# Controller_-_ESP32_Wroom_-_Rev_0_9.net
KiCad netlist of a schematic drawn in EAGLE
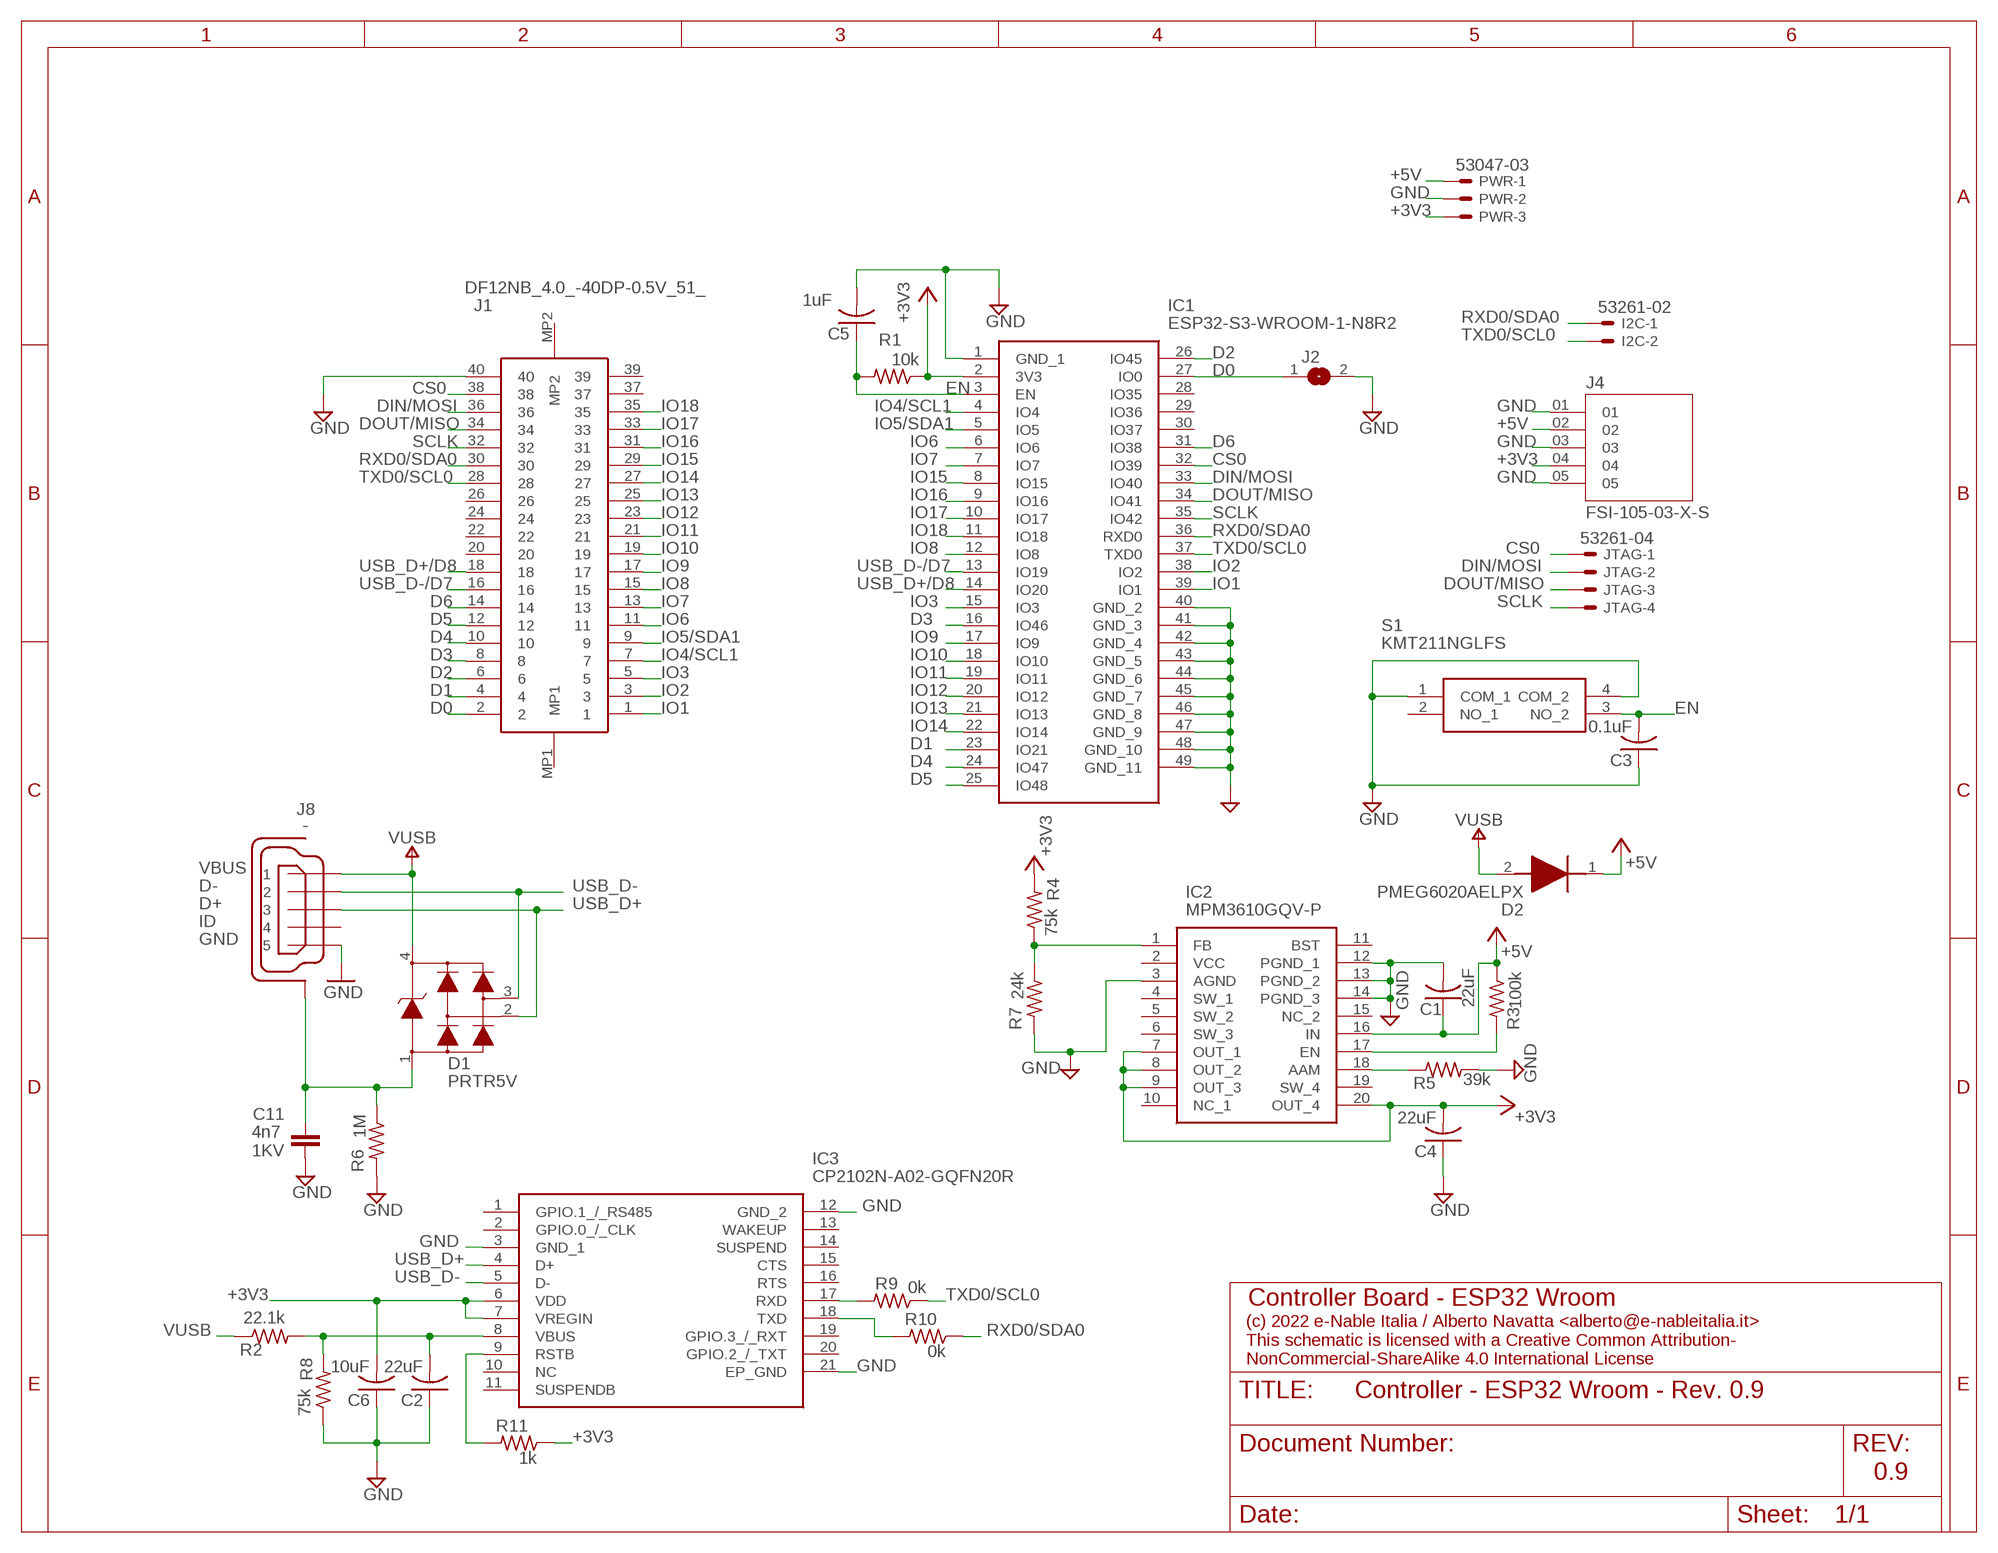
[diagram p0: schematic, sheet 1]

(export (version "E")
  (design (tool "Eeschema 10.0.6"))
  (components
    (comp (ref "C1")
      (value "22uF")
      (footprint "eagle-import:C0603")
      (libsource (lib "eagle-import") (part "C-USC0603"))
    )
    (comp (ref "C2")
      (value "22uF")
      (footprint "eagle-import:C0402")
      (libsource (lib "eagle-import") (part "C-USC0402"))
    )
    (comp (ref "C3")
      (value "0.1uF")
      (footprint "eagle-import:C0402")
      (libsource (lib "eagle-import") (part "C-USC0402"))
    )
    (comp (ref "C4")
      (value "22uF")
      (footprint "eagle-import:C0603")
      (libsource (lib "eagle-import") (part "C-USC0603"))
    )
    (comp (ref "C5")
      (value "1uF")
      (footprint "eagle-import:C0402")
      (libsource (lib "eagle-import") (part "C-USC0402"))
    )
    (comp (ref "C6")
      (value "10uF")
      (footprint "eagle-import:C0402")
      (libsource (lib "eagle-import") (part "C-USC0402"))
    )
    (comp (ref "C11")
      (value "4n7")
      (footprint "eagle-import:0805-R2013X50N")
      (fields (field (name "MANUFACTURER") "Kemet") (field (name "VOLTAGE") "1KV"))
      (libsource (lib "eagle-import") (part "C-08054.7NF"))
    )
    (comp (ref "D1")
      (value "PRTR5V")
      (footprint "eagle-import:SOT190P230X110-4N")
      (fields (field (name "MANUFACTURER") "NXP"))
      (libsource (lib "eagle-import") (part "PRTR5V0U2X,215"))
    )
    (comp (ref "D2")
      (value "PMEG6020AELPX")
      (footprint "eagle-import:SODFL4725X110N")
      (fields (field (name "MOUSER_PART_NUMBER") "771-PMEG6020AELPX"))
      (libsource (lib "eagle-import") (part "PMEG6020AELPX"))
    )
    (comp (ref "I2C")
      (value "53261-02")
      (footprint "eagle-import:53261-02")
      (fields (field (name "MF") "MOLEX"))
      (libsource (lib "eagle-import") (part "53?-02261"))
    )
    (comp (ref "IC1")
      (value "ESP32-S3-WROOM-1-N8R2")
      (footprint "eagle-import:ESP32S3WROOM1N8R2")
      (fields (field (name "MOUSER_PART_NUMBER") "356-ESP32-S3WRM1N8R2"))
      (libsource (lib "eagle-import") (part "ESP32-S3-WROOM-1-N8R2"))
    )
    (comp (ref "IC2")
      (value "MPM3610GQV-P")
      (footprint "eagle-import:MPM3610GQVP")
      (fields (field (name "MOUSER_PART_NUMBER") "946-MPM3610GQV-P"))
      (libsource (lib "eagle-import") (part "MPM3610GQV-P"))
    )
    (comp (ref "IC3")
      (value "CP2102N-A02-GQFN20R")
      (footprint "eagle-import:CP2102NA02GQFN20")
      (fields (field (name "MOUSER_PART_NUMBER") "634-CP2102NA02QFN20R"))
      (libsource (lib "eagle-import") (part "CP2102N-A02-GQFN20R"))
    )
    (comp (ref "J1")
      (value "DF12NB_4.0_-40DP-0.5V_51_")
      (footprint "eagle-import:DF12NB4040DP05V51")
      (fields
        (field (name "MANUFACTURER_PART_NUMBER") "DF12NB(4.0)-40DP-0.5V(51)")
        (field (name "MOUSER_PART_NUMBER") "798-DF12NB4040DP0551")
      )
      (libsource (lib "eagle-import") (part "DF12NB_4.0_-40DP-0.5V_51_"))
    )
    (comp (ref "J2") (value "SJ") (footprint "eagle-import:SJ") (libsource (lib "eagle-import") (part "SJ")))
    (comp (ref "J4")
      (value "FSI-105-03-X-S")
      (footprint "eagle-import:SAMTEC_FSI-105-03-X-S")
      (fields (field (name "MF") "Samtec") (field (name "MP") "FSI-105-03-G-S"))
      (libsource (lib "eagle-import") (part "FSI-105-03-X-S"))
    )
    (comp (ref "J8")
      (value "-")
      (footprint "eagle-import:ZX62-AB-5PA")
      (fields (field (name "MANUFACTURER") "Hirose"))
      (libsource (lib "eagle-import") (part "USB-MICRO"))
    )
    (comp (ref "JTAG")
      (value "53261-04")
      (footprint "eagle-import:53261-04")
      (fields (field (name "MF") "MOLEX"))
      (libsource (lib "eagle-import") (part "53?-04261"))
    )
    (comp (ref "PWR")
      (value "53047-03")
      (footprint "eagle-import:53047-03")
      (fields (field (name "MF") "MOLEX") (field (name "MPN") "530470310"))
      (libsource (lib "eagle-import") (part "53?-03047"))
    )
    (comp (ref "R1")
      (value "10k")
      (footprint "eagle-import:R0402")
      (libsource (lib "eagle-import") (part "R-US_R0402"))
    )
    (comp (ref "R2")
      (value "22.1k")
      (footprint "eagle-import:R0402")
      (libsource (lib "eagle-import") (part "R-US_R0402"))
    )
    (comp (ref "R3")
      (value "100k")
      (footprint "eagle-import:R0402")
      (libsource (lib "eagle-import") (part "R-US_R0402"))
    )
    (comp (ref "R4")
      (value "75k")
      (footprint "eagle-import:R0402")
      (libsource (lib "eagle-import") (part "R-US_R0402"))
    )
    (comp (ref "R5")
      (value "39k")
      (footprint "eagle-import:R0402")
      (libsource (lib "eagle-import") (part "R-US_R0402"))
    )
    (comp (ref "R6")
      (value "1M")
      (footprint "eagle-import:R0402")
      (libsource (lib "eagle-import") (part "R-US_R0402"))
    )
    (comp (ref "R7")
      (value "24k")
      (footprint "eagle-import:R0402")
      (libsource (lib "eagle-import") (part "R-US_R0402"))
    )
    (comp (ref "R8")
      (value "75k")
      (footprint "eagle-import:R0402")
      (libsource (lib "eagle-import") (part "R-US_R0402"))
    )
    (comp (ref "R9")
      (value "0k")
      (footprint "eagle-import:R0402")
      (libsource (lib "eagle-import") (part "R-US_R0402"))
    )
    (comp (ref "R10")
      (value "0k")
      (footprint "eagle-import:R0402")
      (libsource (lib "eagle-import") (part "R-US_R0402"))
    )
    (comp (ref "R11")
      (value "1k")
      (footprint "eagle-import:R0402")
      (libsource (lib "eagle-import") (part "R-US_R0402"))
    )
    (comp (ref "S1")
      (value "KMT211NGLFS")
      (footprint "eagle-import:KMT211NGLFS")
      (fields (field (name "MOUSER_PART_NUMBER") "611-KMT211NGLFS"))
      (libsource (lib "eagle-import") (part "KMT211NGLFS"))
    )
  )
  (nets
    (net (code "1") (name "+3V3") (class "Default")
      (node (ref "C4") (pin "2") (pinfunction "2_2") (pintype "passive"))
      (node (ref "C6") (pin "2") (pinfunction "2_2") (pintype "passive"))
      (node (ref "IC1") (pin "2") (pinfunction "3V3_2") (pintype "bidirectional"))
      (node (ref "IC2") (pin "20") (pinfunction "OUT_4_20") (pintype "bidirectional"))
      (node (ref "IC2") (pin "7") (pinfunction "OUT_1_7") (pintype "bidirectional"))
      (node (ref "IC2") (pin "8") (pinfunction "OUT_2_8") (pintype "bidirectional"))
      (node (ref "IC2") (pin "9") (pinfunction "OUT_3_9") (pintype "bidirectional"))
      (node (ref "IC3") (pin "6") (pinfunction "VDD_6") (pintype "bidirectional"))
      (node (ref "IC3") (pin "7") (pinfunction "VREGIN_7") (pintype "bidirectional"))
      (node (ref "J4") (pin "04") (pinfunction "04_04") (pintype "passive"))
      (node (ref "PWR") (pin "3") (pinfunction "S_3") (pintype "passive"))
      (node (ref "R1") (pin "1") (pinfunction "1_1") (pintype "passive"))
      (node (ref "R11") (pin "1") (pinfunction "1_1") (pintype "passive"))
      (node (ref "R4") (pin "2") (pinfunction "2_2") (pintype "passive"))
    )
    (net (code "2") (name "+5V") (class "Default")
      (node (ref "C1") (pin "1") (pinfunction "1_1") (pintype "passive"))
      (node (ref "D2") (pin "1") (pinfunction "K_1") (pintype "bidirectional"))
      (node (ref "IC2") (pin "16") (pinfunction "IN_16") (pintype "bidirectional"))
      (node (ref "J4") (pin "02") (pinfunction "02_02") (pintype "passive"))
      (node (ref "PWR") (pin "1") (pinfunction "S_1") (pintype "passive"))
      (node (ref "R3") (pin "1") (pinfunction "1_1") (pintype "passive"))
    )
    (net (code "3") (name "/CS0") (class "Default")
      (node (ref "IC1") (pin "32") (pinfunction "IO39_32") (pintype "bidirectional"))
      (node (ref "J1") (pin "38") (pinfunction "38_38") (pintype "bidirectional"))
      (node (ref "JTAG") (pin "1") (pinfunction "S_1") (pintype "passive"))
    )
    (net (code "4") (name "/D0") (class "Default")
      (node (ref "IC1") (pin "27") (pinfunction "IO0_27") (pintype "bidirectional"))
      (node (ref "J1") (pin "2") (pinfunction "2_2") (pintype "bidirectional"))
      (node (ref "J2") (pin "1") (pinfunction "1_1") (pintype "passive"))
    )
    (net (code "5") (name "/D1") (class "Default")
      (node (ref "IC1") (pin "23") (pinfunction "IO21_23") (pintype "bidirectional"))
      (node (ref "J1") (pin "4") (pinfunction "4_4") (pintype "bidirectional"))
    )
    (net (code "6") (name "/D2") (class "Default")
      (node (ref "IC1") (pin "26") (pinfunction "IO45_26") (pintype "bidirectional"))
      (node (ref "J1") (pin "6") (pinfunction "6_6") (pintype "bidirectional"))
    )
    (net (code "7") (name "/D3") (class "Default")
      (node (ref "IC1") (pin "16") (pinfunction "IO46_16") (pintype "bidirectional"))
      (node (ref "J1") (pin "8") (pinfunction "8_8") (pintype "bidirectional"))
    )
    (net (code "8") (name "/D4") (class "Default")
      (node (ref "IC1") (pin "24") (pinfunction "IO47_24") (pintype "bidirectional"))
      (node (ref "J1") (pin "10") (pinfunction "10_10") (pintype "bidirectional"))
    )
    (net (code "9") (name "/D5") (class "Default")
      (node (ref "IC1") (pin "25") (pinfunction "IO48_25") (pintype "bidirectional"))
      (node (ref "J1") (pin "12") (pinfunction "12_12") (pintype "bidirectional"))
    )
    (net (code "10") (name "/D6") (class "Default")
      (node (ref "IC1") (pin "31") (pinfunction "IO38_31") (pintype "bidirectional"))
      (node (ref "J1") (pin "14") (pinfunction "14_14") (pintype "bidirectional"))
    )
    (net (code "11") (name "/DIN{slash}MOSI") (class "Default")
      (node (ref "IC1") (pin "33") (pinfunction "IO40_33") (pintype "bidirectional"))
      (node (ref "J1") (pin "36") (pinfunction "36_36") (pintype "bidirectional"))
      (node (ref "JTAG") (pin "2") (pinfunction "S_2") (pintype "passive"))
    )
    (net (code "12") (name "/DOUT{slash}MISO") (class "Default")
      (node (ref "IC1") (pin "34") (pinfunction "IO41_34") (pintype "bidirectional"))
      (node (ref "J1") (pin "34") (pinfunction "34_34") (pintype "bidirectional"))
      (node (ref "JTAG") (pin "3") (pinfunction "S_3") (pintype "passive"))
    )
    (net (code "13") (name "/EN") (class "Default")
      (node (ref "C3") (pin "2") (pinfunction "2_2") (pintype "passive"))
      (node (ref "C5") (pin "1") (pinfunction "1_1") (pintype "passive"))
      (node (ref "IC1") (pin "3") (pinfunction "EN_3") (pintype "bidirectional"))
      (node (ref "R1") (pin "2") (pinfunction "2_2") (pintype "passive"))
      (node (ref "S1") (pin "3") (pinfunction "NO_2_3") (pintype "bidirectional"))
    )
    (net (code "14") (name "/IO1") (class "Default")
      (node (ref "IC1") (pin "39") (pinfunction "IO1_39") (pintype "bidirectional"))
      (node (ref "J1") (pin "1") (pinfunction "1_1") (pintype "bidirectional"))
    )
    (net (code "15") (name "/IO2") (class "Default")
      (node (ref "IC1") (pin "38") (pinfunction "IO2_38") (pintype "bidirectional"))
      (node (ref "J1") (pin "3") (pinfunction "3_3") (pintype "bidirectional"))
    )
    (net (code "16") (name "/IO3") (class "Default")
      (node (ref "IC1") (pin "15") (pinfunction "IO3_15") (pintype "bidirectional"))
      (node (ref "J1") (pin "5") (pinfunction "5_5") (pintype "bidirectional"))
    )
    (net (code "17") (name "/IO4{slash}SCL1") (class "Default")
      (node (ref "IC1") (pin "4") (pinfunction "IO4_4") (pintype "bidirectional"))
      (node (ref "J1") (pin "7") (pinfunction "7_7") (pintype "bidirectional"))
    )
    (net (code "18") (name "/IO5{slash}SDA1") (class "Default")
      (node (ref "IC1") (pin "5") (pinfunction "IO5_5") (pintype "bidirectional"))
      (node (ref "J1") (pin "9") (pinfunction "9_9") (pintype "bidirectional"))
    )
    (net (code "19") (name "/IO6") (class "Default")
      (node (ref "IC1") (pin "6") (pinfunction "IO6_6") (pintype "bidirectional"))
      (node (ref "J1") (pin "11") (pinfunction "11_11") (pintype "bidirectional"))
    )
    (net (code "20") (name "/IO7") (class "Default")
      (node (ref "IC1") (pin "7") (pinfunction "IO7_7") (pintype "bidirectional"))
      (node (ref "J1") (pin "13") (pinfunction "13_13") (pintype "bidirectional"))
    )
    (net (code "21") (name "/IO8") (class "Default")
      (node (ref "IC1") (pin "12") (pinfunction "IO8_12") (pintype "bidirectional"))
      (node (ref "J1") (pin "15") (pinfunction "15_15") (pintype "bidirectional"))
    )
    (net (code "22") (name "/IO9") (class "Default")
      (node (ref "IC1") (pin "17") (pinfunction "IO9_17") (pintype "bidirectional"))
      (node (ref "J1") (pin "17") (pinfunction "17_17") (pintype "bidirectional"))
    )
    (net (code "23") (name "/IO10") (class "Default")
      (node (ref "IC1") (pin "18") (pinfunction "IO10_18") (pintype "bidirectional"))
      (node (ref "J1") (pin "19") (pinfunction "19_19") (pintype "bidirectional"))
    )
    (net (code "24") (name "/IO11") (class "Default")
      (node (ref "IC1") (pin "19") (pinfunction "IO11_19") (pintype "bidirectional"))
      (node (ref "J1") (pin "21") (pinfunction "21_21") (pintype "bidirectional"))
    )
    (net (code "25") (name "/IO12") (class "Default")
      (node (ref "IC1") (pin "20") (pinfunction "IO12_20") (pintype "bidirectional"))
      (node (ref "J1") (pin "23") (pinfunction "23_23") (pintype "bidirectional"))
    )
    (net (code "26") (name "/IO13") (class "Default")
      (node (ref "IC1") (pin "21") (pinfunction "IO13_21") (pintype "bidirectional"))
      (node (ref "J1") (pin "25") (pinfunction "25_25") (pintype "bidirectional"))
    )
    (net (code "27") (name "/IO14") (class "Default")
      (node (ref "IC1") (pin "22") (pinfunction "IO14_22") (pintype "bidirectional"))
      (node (ref "J1") (pin "27") (pinfunction "27_27") (pintype "bidirectional"))
    )
    (net (code "28") (name "/IO15") (class "Default")
      (node (ref "IC1") (pin "8") (pinfunction "IO15_8") (pintype "bidirectional"))
      (node (ref "J1") (pin "29") (pinfunction "29_29") (pintype "bidirectional"))
    )
    (net (code "29") (name "/IO16") (class "Default")
      (node (ref "IC1") (pin "9") (pinfunction "IO16_9") (pintype "bidirectional"))
      (node (ref "J1") (pin "31") (pinfunction "31_31") (pintype "bidirectional"))
    )
    (net (code "30") (name "/IO17") (class "Default")
      (node (ref "IC1") (pin "10") (pinfunction "IO17_10") (pintype "bidirectional"))
      (node (ref "J1") (pin "33") (pinfunction "33_33") (pintype "bidirectional"))
    )
    (net (code "31") (name "/IO18") (class "Default")
      (node (ref "IC1") (pin "11") (pinfunction "IO18_11") (pintype "bidirectional"))
      (node (ref "J1") (pin "35") (pinfunction "35_35") (pintype "bidirectional"))
    )
    (net (code "32") (name "/RXD0{slash}SDA0") (class "Default")
      (node (ref "I2C") (pin "1") (pinfunction "S_1") (pintype "passive"))
      (node (ref "IC1") (pin "36") (pinfunction "RXD0_36") (pintype "bidirectional"))
      (node (ref "J1") (pin "30") (pinfunction "30_30") (pintype "bidirectional"))
      (node (ref "R10") (pin "1") (pinfunction "1_1") (pintype "passive"))
    )
    (net (code "33") (name "/SCLK") (class "Default")
      (node (ref "IC1") (pin "35") (pinfunction "IO42_35") (pintype "bidirectional"))
      (node (ref "J1") (pin "32") (pinfunction "32_32") (pintype "bidirectional"))
      (node (ref "JTAG") (pin "4") (pinfunction "S_4") (pintype "passive"))
    )
    (net (code "34") (name "/TXD0{slash}SCL0") (class "Default")
      (node (ref "I2C") (pin "2") (pinfunction "S_2") (pintype "passive"))
      (node (ref "IC1") (pin "37") (pinfunction "TXD0_37") (pintype "bidirectional"))
      (node (ref "J1") (pin "28") (pinfunction "28_28") (pintype "bidirectional"))
      (node (ref "R9") (pin "1") (pinfunction "1_1") (pintype "passive"))
    )
    (net (code "35") (name "/USB_D+") (class "Default")
      (node (ref "D1") (pin "2") (pinfunction "2_2") (pintype "passive"))
      (node (ref "IC3") (pin "4") (pinfunction "D+_4") (pintype "bidirectional"))
      (node (ref "J8") (pin "3") (pinfunction "3_3") (pintype "passive"))
    )
    (net (code "36") (name "/USB_D+{slash}D8") (class "Default")
      (node (ref "IC1") (pin "14") (pinfunction "IO20_14") (pintype "bidirectional"))
      (node (ref "J1") (pin "18") (pinfunction "18_18") (pintype "bidirectional"))
    )
    (net (code "37") (name "/USB_D-") (class "Default")
      (node (ref "D1") (pin "3") (pinfunction "3_3") (pintype "passive"))
      (node (ref "IC3") (pin "5") (pinfunction "D-_5") (pintype "bidirectional"))
      (node (ref "J8") (pin "2") (pinfunction "2_2") (pintype "passive"))
    )
    (net (code "38") (name "/USB_D-{slash}D7") (class "Default")
      (node (ref "IC1") (pin "13") (pinfunction "IO19_13") (pintype "bidirectional"))
      (node (ref "J1") (pin "16") (pinfunction "16_16") (pintype "bidirectional"))
    )
    (net (code "39") (name "GND") (class "Default")
      (node (ref "C1") (pin "2") (pinfunction "2_2") (pintype "passive"))
      (node (ref "C11") (pin "2") (pinfunction "2_2") (pintype "passive"))
      (node (ref "C2") (pin "1") (pinfunction "1_1") (pintype "passive"))
      (node (ref "C3") (pin "1") (pinfunction "1_1") (pintype "passive"))
      (node (ref "C4") (pin "1") (pinfunction "1_1") (pintype "passive"))
      (node (ref "C5") (pin "2") (pinfunction "2_2") (pintype "passive"))
      (node (ref "C6") (pin "1") (pinfunction "1_1") (pintype "passive"))
      (node (ref "IC1") (pin "1") (pinfunction "GND_1_1") (pintype "bidirectional"))
      (node (ref "IC1") (pin "40") (pinfunction "GND_2_40") (pintype "bidirectional"))
      (node (ref "IC1") (pin "41") (pinfunction "GND_3_41") (pintype "bidirectional"))
      (node (ref "IC1") (pin "42") (pinfunction "GND_4_42") (pintype "bidirectional"))
      (node (ref "IC1") (pin "43") (pinfunction "GND_5_43") (pintype "bidirectional"))
      (node (ref "IC1") (pin "44") (pinfunction "GND_6_44") (pintype "bidirectional"))
      (node (ref "IC1") (pin "45") (pinfunction "GND_7_45") (pintype "bidirectional"))
      (node (ref "IC1") (pin "46") (pinfunction "GND_8_46") (pintype "bidirectional"))
      (node (ref "IC1") (pin "47") (pinfunction "GND_9_47") (pintype "bidirectional"))
      (node (ref "IC1") (pin "48") (pinfunction "GND_10_48") (pintype "bidirectional"))
      (node (ref "IC1") (pin "49") (pinfunction "GND_11_49") (pintype "bidirectional"))
      (node (ref "IC2") (pin "12") (pinfunction "PGND_1_12") (pintype "bidirectional"))
      (node (ref "IC2") (pin "13") (pinfunction "PGND_2_13") (pintype "bidirectional"))
      (node (ref "IC2") (pin "14") (pinfunction "PGND_3_14") (pintype "bidirectional"))
      (node (ref "IC2") (pin "3") (pinfunction "AGND_3") (pintype "bidirectional"))
      (node (ref "IC3") (pin "12") (pinfunction "GND_2_12") (pintype "bidirectional"))
      (node (ref "IC3") (pin "21") (pinfunction "EP_GND_21") (pintype "bidirectional"))
      (node (ref "IC3") (pin "3") (pinfunction "GND_1_3") (pintype "bidirectional"))
      (node (ref "J1") (pin "40") (pinfunction "40_40") (pintype "bidirectional"))
      (node (ref "J2") (pin "2") (pinfunction "2_2") (pintype "passive"))
      (node (ref "J4") (pin "01") (pinfunction "01_01") (pintype "passive"))
      (node (ref "J4") (pin "03") (pinfunction "03_03") (pintype "passive"))
      (node (ref "J4") (pin "05") (pinfunction "05_05") (pintype "passive"))
      (node (ref "J8") (pin "5") (pinfunction "5_5") (pintype "passive"))
      (node (ref "PWR") (pin "2") (pinfunction "S_2") (pintype "passive"))
      (node (ref "R5") (pin "2") (pinfunction "2_2") (pintype "passive"))
      (node (ref "R6") (pin "2") (pinfunction "2_2") (pintype "passive"))
      (node (ref "R7") (pin "2") (pinfunction "2_2") (pintype "passive"))
      (node (ref "R8") (pin "1") (pinfunction "1_1") (pintype "passive"))
      (node (ref "S1") (pin "1") (pinfunction "COM_1_1") (pintype "bidirectional"))
      (node (ref "S1") (pin "4") (pinfunction "COM_2_4") (pintype "bidirectional"))
    )
    (net (code "40") (name "Net-(C11-Pad1)") (class "Default")
      (node (ref "C11") (pin "1") (pinfunction "1_1") (pintype "passive"))
      (node (ref "D1") (pin "1") (pinfunction "1_1") (pintype "passive"))
      (node (ref "J8") (pin "10") (pinfunction "SH_10") (pintype "passive"))
      (node (ref "J8") (pin "11") (pinfunction "SH_11") (pintype "passive"))
      (node (ref "J8") (pin "6") (pinfunction "SH_6") (pintype "passive"))
      (node (ref "J8") (pin "7") (pinfunction "SH_7") (pintype "passive"))
      (node (ref "J8") (pin "8") (pinfunction "SH_8") (pintype "passive"))
      (node (ref "J8") (pin "9") (pinfunction "SH_9") (pintype "passive"))
      (node (ref "R6") (pin "1") (pinfunction "1_1") (pintype "passive"))
    )
    (net (code "41") (name "Net-(IC2-AAM)") (class "Default")
      (node (ref "IC2") (pin "18") (pinfunction "AAM_18") (pintype "bidirectional"))
      (node (ref "R5") (pin "1") (pinfunction "1_1") (pintype "passive"))
    )
    (net (code "42") (name "Net-(IC2-EN)") (class "Default")
      (node (ref "IC2") (pin "17") (pinfunction "EN_17") (pintype "bidirectional"))
      (node (ref "R3") (pin "2") (pinfunction "2_2") (pintype "passive"))
    )
    (net (code "43") (name "Net-(IC2-FB)") (class "Default")
      (node (ref "IC2") (pin "1") (pinfunction "FB_1") (pintype "bidirectional"))
      (node (ref "R4") (pin "1") (pinfunction "1_1") (pintype "passive"))
      (node (ref "R7") (pin "1") (pinfunction "1_1") (pintype "passive"))
    )
    (net (code "44") (name "Net-(IC3-RSTB)") (class "Default")
      (node (ref "IC3") (pin "9") (pinfunction "RSTB_9") (pintype "bidirectional"))
      (node (ref "R11") (pin "2") (pinfunction "2_2") (pintype "passive"))
    )
    (net (code "45") (name "Net-(IC3-RXD)") (class "Default")
      (node (ref "IC3") (pin "17") (pinfunction "RXD_17") (pintype "bidirectional"))
      (node (ref "R9") (pin "2") (pinfunction "2_2") (pintype "passive"))
    )
    (net (code "46") (name "Net-(IC3-TXD)") (class "Default")
      (node (ref "IC3") (pin "18") (pinfunction "TXD_18") (pintype "bidirectional"))
      (node (ref "R10") (pin "2") (pinfunction "2_2") (pintype "passive"))
    )
    (net (code "47") (name "Net-(IC3-VBUS)") (class "Default")
      (node (ref "C2") (pin "2") (pinfunction "2_2") (pintype "passive"))
      (node (ref "IC3") (pin "8") (pinfunction "VBUS_8") (pintype "bidirectional"))
      (node (ref "R2") (pin "2") (pinfunction "2_2") (pintype "passive"))
      (node (ref "R8") (pin "2") (pinfunction "2_2") (pintype "passive"))
    )
    (net (code "48") (name "VUSB") (class "Default")
      (node (ref "D1") (pin "4") (pinfunction "4_4") (pintype "passive"))
      (node (ref "D2") (pin "2") (pinfunction "A_2") (pintype "bidirectional"))
      (node (ref "J8") (pin "1") (pinfunction "1_1") (pintype "passive"))
      (node (ref "R2") (pin "1") (pinfunction "1_1") (pintype "passive"))
    )
    (net (code "49") (name "unconnected-(IC1-IO35-Pad28)") (class "Default")
      (node (ref "IC1") (pin "28") (pinfunction "IO35_28") (pintype "bidirectional"))
    )
    (net (code "50") (name "unconnected-(IC1-IO36-Pad29)") (class "Default")
      (node (ref "IC1") (pin "29") (pinfunction "IO36_29") (pintype "bidirectional"))
    )
    (net (code "51") (name "unconnected-(IC1-IO37-Pad30)") (class "Default")
      (node (ref "IC1") (pin "30") (pinfunction "IO37_30") (pintype "bidirectional"))
    )
    (net (code "52") (name "unconnected-(IC2-BST-Pad11)") (class "Default")
      (node (ref "IC2") (pin "11") (pinfunction "BST_11") (pintype "bidirectional"))
    )
    (net (code "53") (name "unconnected-(IC2-NC_1-Pad10)") (class "Default")
      (node (ref "IC2") (pin "10") (pinfunction "NC_1_10") (pintype "bidirectional"))
    )
    (net (code "54") (name "unconnected-(IC2-NC_2-Pad15)") (class "Default")
      (node (ref "IC2") (pin "15") (pinfunction "NC_2_15") (pintype "bidirectional"))
    )
    (net (code "55") (name "unconnected-(IC2-SW_1-Pad4)") (class "Default")
      (node (ref "IC2") (pin "4") (pinfunction "SW_1_4") (pintype "bidirectional"))
    )
    (net (code "56") (name "unconnected-(IC2-SW_2-Pad5)") (class "Default")
      (node (ref "IC2") (pin "5") (pinfunction "SW_2_5") (pintype "bidirectional"))
    )
    (net (code "57") (name "unconnected-(IC2-SW_3-Pad6)") (class "Default")
      (node (ref "IC2") (pin "6") (pinfunction "SW_3_6") (pintype "bidirectional"))
    )
    (net (code "58") (name "unconnected-(IC2-SW_4-Pad19)") (class "Default")
      (node (ref "IC2") (pin "19") (pinfunction "SW_4_19") (pintype "bidirectional"))
    )
    (net (code "59") (name "unconnected-(IC2-VCC-Pad2)") (class "Default")
      (node (ref "IC2") (pin "2") (pinfunction "VCC_2") (pintype "bidirectional"))
    )
    (net (code "60") (name "unconnected-(IC3-CTS-Pad15)") (class "Default")
      (node (ref "IC3") (pin "15") (pinfunction "CTS_15") (pintype "bidirectional"))
    )
    (net (code "61") (name "unconnected-(IC3-GPIO.0_{slash}_CLK-Pad2)") (class "Default")
      (node (ref "IC3") (pin "2") (pinfunction "GPIO.0_/_CLK_2") (pintype "bidirectional"))
    )
    (net (code "62") (name "unconnected-(IC3-GPIO.1_{slash}_RS485-Pad1)") (class "Default")
      (node (ref "IC3") (pin "1") (pinfunction "GPIO.1_/_RS485_1") (pintype "bidirectional"))
    )
    (net (code "63") (name "unconnected-(IC3-GPIO.2_{slash}_TXT-Pad20)") (class "Default")
      (node (ref "IC3") (pin "20") (pinfunction "GPIO.2_/_TXT_20") (pintype "bidirectional"))
    )
    (net (code "64") (name "unconnected-(IC3-GPIO.3_{slash}_RXT-Pad19)") (class "Default")
      (node (ref "IC3") (pin "19") (pinfunction "GPIO.3_/_RXT_19") (pintype "bidirectional"))
    )
    (net (code "65") (name "unconnected-(IC3-NC-Pad10)") (class "Default")
      (node (ref "IC3") (pin "10") (pinfunction "NC_10") (pintype "no_connect"))
    )
    (net (code "66") (name "unconnected-(IC3-RTS-Pad16)") (class "Default")
      (node (ref "IC3") (pin "16") (pinfunction "RTS_16") (pintype "bidirectional"))
    )
    (net (code "67") (name "unconnected-(IC3-SUSPEND-Pad14)") (class "Default")
      (node (ref "IC3") (pin "14") (pinfunction "SUSPEND_14") (pintype "bidirectional"))
    )
    (net (code "68") (name "unconnected-(IC3-SUSPENDB-Pad11)") (class "Default")
      (node (ref "IC3") (pin "11") (pinfunction "SUSPENDB_11") (pintype "bidirectional"))
    )
    (net (code "69") (name "unconnected-(IC3-WAKEUP-Pad13)") (class "Default")
      (node (ref "IC3") (pin "13") (pinfunction "WAKEUP_13") (pintype "bidirectional"))
    )
    (net (code "70") (name "unconnected-(J1-Pad20)") (class "Default")
      (node (ref "J1") (pin "20") (pinfunction "20_20") (pintype "bidirectional"))
    )
    (net (code "71") (name "unconnected-(J1-Pad22)") (class "Default")
      (node (ref "J1") (pin "22") (pinfunction "22_22") (pintype "bidirectional"))
    )
    (net (code "72") (name "unconnected-(J1-Pad24)") (class "Default")
      (node (ref "J1") (pin "24") (pinfunction "24_24") (pintype "bidirectional"))
    )
    (net (code "73") (name "unconnected-(J1-Pad26)") (class "Default")
      (node (ref "J1") (pin "26") (pinfunction "26_26") (pintype "bidirectional"))
    )
    (net (code "74") (name "unconnected-(J1-Pad37)") (class "Default")
      (node (ref "J1") (pin "37") (pinfunction "37_37") (pintype "bidirectional"))
    )
    (net (code "75") (name "unconnected-(J1-Pad39)") (class "Default")
      (node (ref "J1") (pin "39") (pinfunction "39_39") (pintype "bidirectional"))
    )
    (net (code "76") (name "unconnected-(J1-PadMP1)") (class "Default")
      (node (ref "J1") (pin "MP1") (pinfunction "MP1_MP1") (pintype "bidirectional"))
    )
    (net (code "77") (name "unconnected-(J1-PadMP2)") (class "Default")
      (node (ref "J1") (pin "MP2") (pinfunction "MP2_MP2") (pintype "bidirectional"))
    )
    (net (code "78") (name "unconnected-(J8-Pad4)") (class "Default")
      (node (ref "J8") (pin "4") (pinfunction "4_4") (pintype "passive"))
    )
    (net (code "79") (name "unconnected-(S1-NO_1-Pad2)") (class "Default")
      (node (ref "S1") (pin "2") (pinfunction "NO_1_2") (pintype "bidirectional"))
    )
  )
)
